# MAX232.net
KiCad netlist of a schematic drawn in Altium Designer
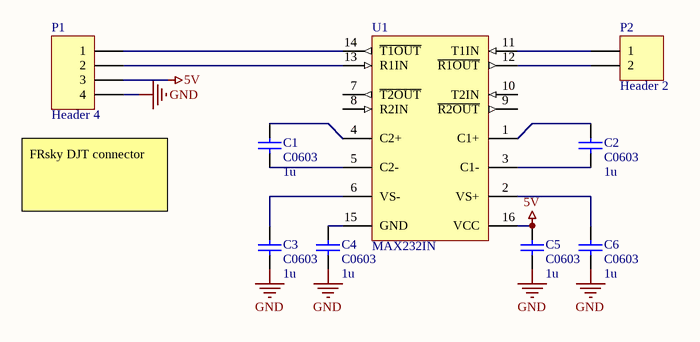
[diagram p0: MAX232.SchDoc]

(export (version "E")
  (design (tool "Eeschema 10.0.6"))
  (components
    (comp (ref "C1")
      (value "1u")
      (footprint "C0603")
      (description "Generic capacitor")
      (libsource (lib "_RLC") (part "Cap"))
    )
    (comp (ref "C2")
      (value "1u")
      (footprint "C0603")
      (description "Generic capacitor")
      (libsource (lib "_RLC") (part "Cap"))
    )
    (comp (ref "C3")
      (value "1u")
      (footprint "C0603")
      (description "Generic capacitor")
      (libsource (lib "_RLC") (part "Cap"))
    )
    (comp (ref "C4")
      (value "1u")
      (footprint "C0603")
      (description "Generic capacitor")
      (libsource (lib "_RLC") (part "Cap"))
    )
    (comp (ref "C5")
      (value "1u")
      (footprint "C0603")
      (description "Generic capacitor")
      (libsource (lib "_RLC") (part "Cap"))
    )
    (comp (ref "C6")
      (value "1u")
      (footprint "C0603")
      (description "Generic capacitor")
      (libsource (lib "_RLC") (part "Cap"))
    )
    (comp (ref "P1")
      (value "Header 4")
      (footprint "HEADER 1X4 FEMALE")
      (description "Header, 4-Pin")
      (fields (field (name "PUBLISHER") "Altium Limited"))
      (libsource (lib "_Connectors") (part "Header 4"))
    )
    (comp (ref "P2")
      (value "Header 2")
      (footprint "HEADER 1X2H Male")
      (description "Header, 2-Pin")
      (fields (field (name "PUBLISHER") "Altium Limited"))
      (libsource (lib "_Connectors") (part "Header 2"))
    )
    (comp (ref "U1")
      (value "MAX232IN")
      (footprint "DIP16")
      (description "Dual EIA-232 Driver / Receiver, -40 to 85 degC, 16-Pin PDIP (N), Pb-Free (RoHS)")
      (libsource (lib "_Microcircuits") (part "MAX232IN"))
    )
  )
  (nets
    (net (code "1") (name "5V") (class "Default")
      (node (ref "C5") (pin "2") (pinfunction "2_2") (pintype "passive"))
      (node (ref "P1") (pin "3") (pinfunction "3_3") (pintype "passive"))
      (node (ref "U1") (pin "16") (pinfunction "VCC_16") (pintype "power_in"))
    )
    (net (code "2") (name "GND") (class "Default")
      (node (ref "C3") (pin "1") (pinfunction "1_1") (pintype "passive"))
      (node (ref "C4") (pin "1") (pinfunction "1_1") (pintype "passive"))
      (node (ref "C5") (pin "1") (pinfunction "1_1") (pintype "passive"))
      (node (ref "C6") (pin "1") (pinfunction "1_1") (pintype "passive"))
      (node (ref "P1") (pin "4") (pinfunction "4_4") (pintype "passive"))
    )
    (net (code "3") (name "Net-(U1-C1+)") (class "Default")
      (node (ref "C2") (pin "2") (pinfunction "2_2") (pintype "passive"))
      (node (ref "U1") (pin "1") (pinfunction "C1+_1") (pintype "passive"))
    )
    (net (code "4") (name "Net-(U1-C1-)") (class "Default")
      (node (ref "C2") (pin "1") (pinfunction "1_1") (pintype "passive"))
      (node (ref "U1") (pin "3") (pinfunction "C1-_3") (pintype "passive"))
    )
    (net (code "5") (name "Net-(U1-C2+)") (class "Default")
      (node (ref "C1") (pin "2") (pinfunction "2_2") (pintype "passive"))
      (node (ref "U1") (pin "4") (pinfunction "C2+_4") (pintype "passive"))
    )
    (net (code "6") (name "Net-(U1-C2-)") (class "Default")
      (node (ref "C1") (pin "1") (pinfunction "1_1") (pintype "passive"))
      (node (ref "U1") (pin "5") (pinfunction "C2-_5") (pintype "passive"))
    )
    (net (code "7") (name "Net-(U1-GND)") (class "Default")
      (node (ref "C4") (pin "2") (pinfunction "2_2") (pintype "passive"))
      (node (ref "U1") (pin "15") (pinfunction "GND_15") (pintype "power_in"))
    )
    (net (code "8") (name "Net-(U1-R1IN)") (class "Default")
      (node (ref "P1") (pin "2") (pinfunction "2_2") (pintype "passive"))
      (node (ref "U1") (pin "13") (pinfunction "R1IN_13") (pintype "input"))
    )
    (net (code "9") (name "Net-(U1-T1IN)") (class "Default")
      (node (ref "P2") (pin "1") (pinfunction "1_1") (pintype "passive"))
      (node (ref "U1") (pin "11") (pinfunction "T1IN_11") (pintype "input"))
    )
    (net (code "10") (name "Net-(U1-VS+)") (class "Default")
      (node (ref "C6") (pin "2") (pinfunction "2_2") (pintype "passive"))
      (node (ref "U1") (pin "2") (pinfunction "VS+_2") (pintype "power_in"))
    )
    (net (code "11") (name "Net-(U1-VS-)") (class "Default")
      (node (ref "C3") (pin "2") (pinfunction "2_2") (pintype "passive"))
      (node (ref "U1") (pin "6") (pinfunction "VS-_6") (pintype "power_in"))
    )
    (net (code "12") (name "Net-(U1-~{R1OUT})") (class "Default")
      (node (ref "P2") (pin "2") (pinfunction "2_2") (pintype "passive"))
      (node (ref "U1") (pin "12") (pinfunction "~{R1OUT}_12") (pintype "output"))
    )
    (net (code "13") (name "Net-(U1-~{T1OUT})") (class "Default")
      (node (ref "P1") (pin "1") (pinfunction "1_1") (pintype "passive"))
      (node (ref "U1") (pin "14") (pinfunction "~{T1OUT}_14") (pintype "output"))
    )
    (net (code "14") (name "unconnected-(U1-R2IN-Pad8)") (class "Default")
      (node (ref "U1") (pin "8") (pinfunction "R2IN_8") (pintype "input"))
    )
    (net (code "15") (name "unconnected-(U1-T2IN-Pad10)") (class "Default")
      (node (ref "U1") (pin "10") (pinfunction "T2IN_10") (pintype "input"))
    )
    (net (code "16") (name "unconnected-(U1-~{R2OUT}-Pad9)") (class "Default")
      (node (ref "U1") (pin "9") (pinfunction "~{R2OUT}_9") (pintype "output"))
    )
    (net (code "17") (name "unconnected-(U1-~{T2OUT}-Pad7)") (class "Default")
      (node (ref "U1") (pin "7") (pinfunction "~{T2OUT}_7") (pintype "output"))
    )
  )
)
